# untitled5.net
KiCad netlist of a schematic drawn in EAGLE
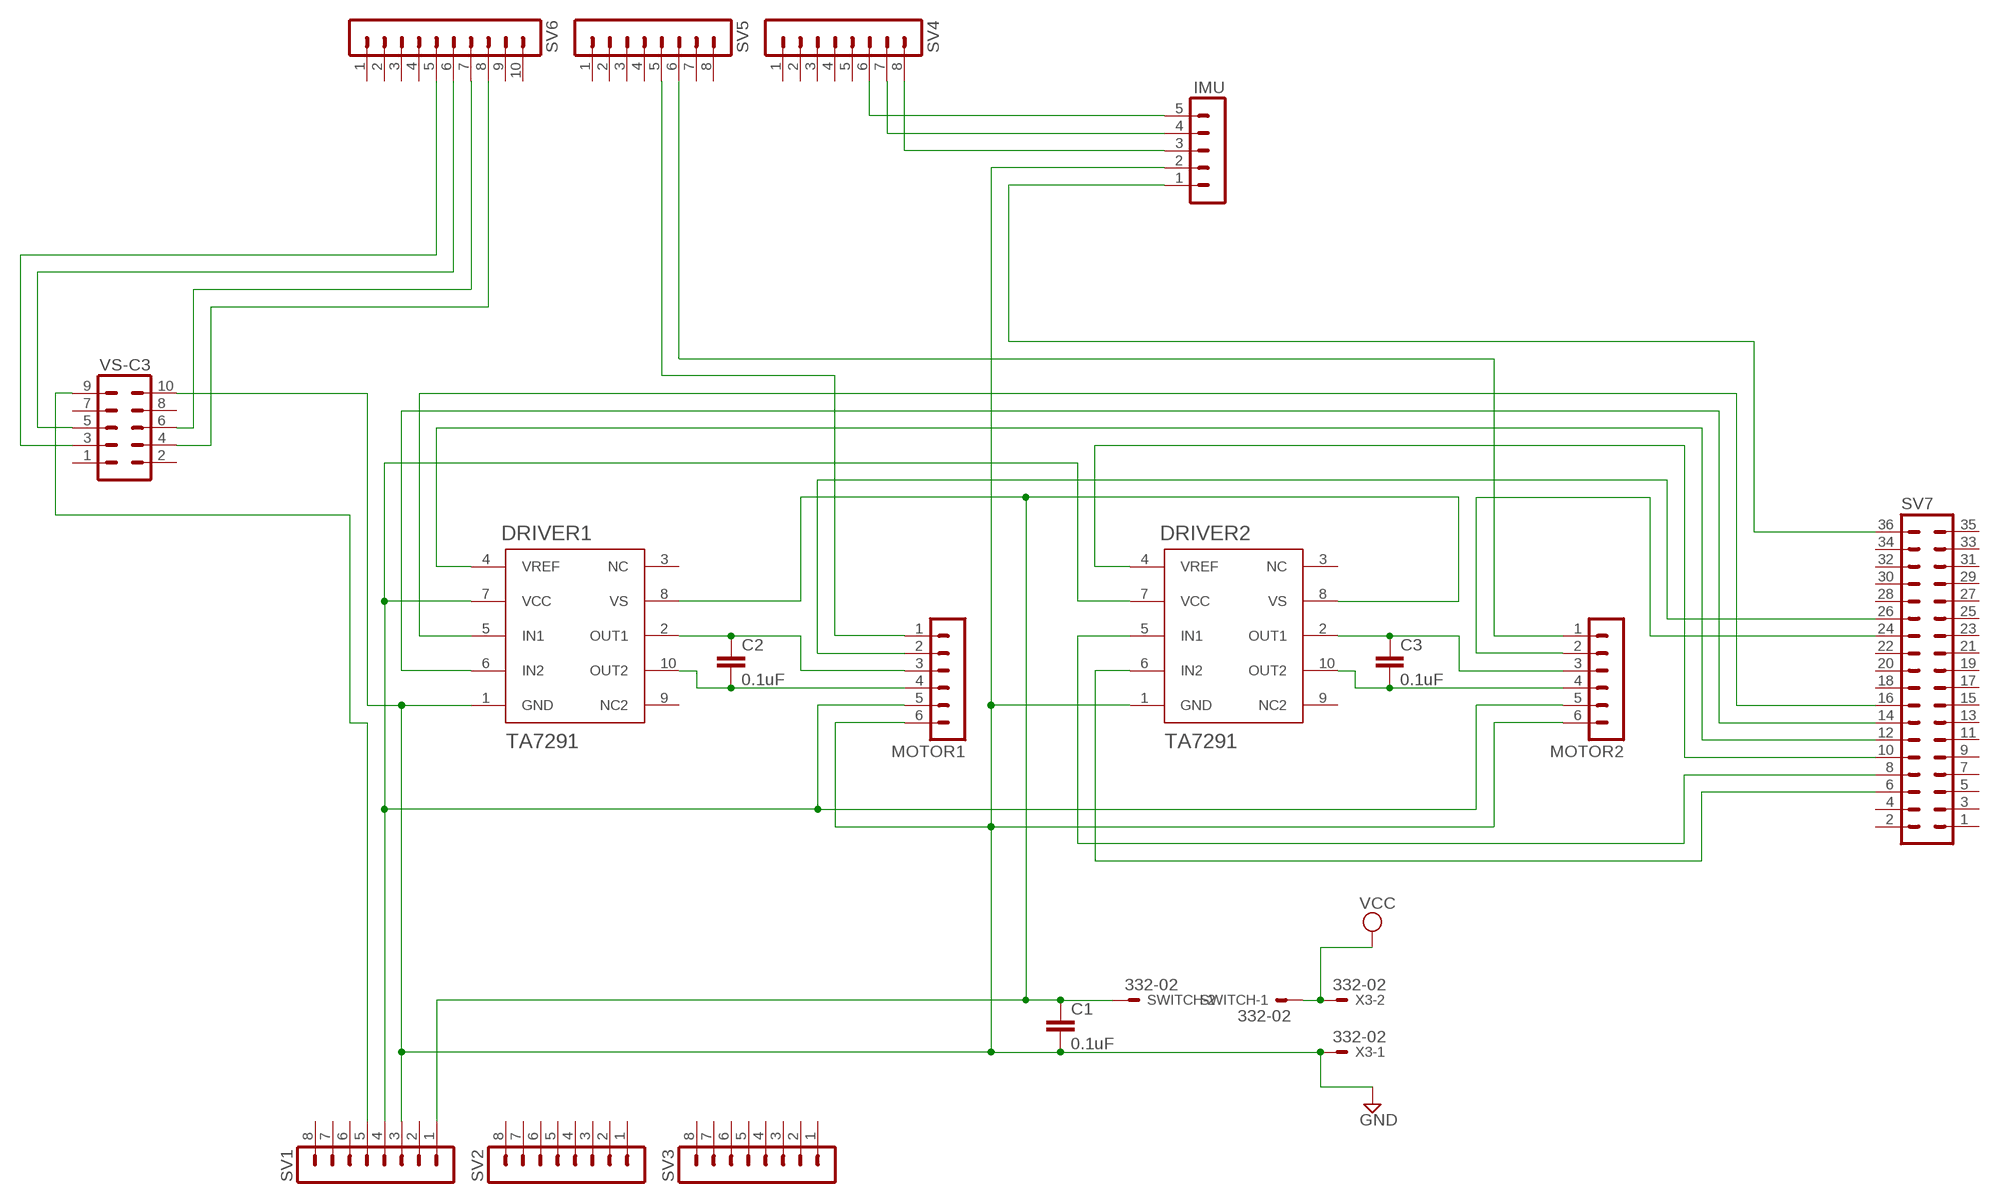
[diagram p0: schematic, sheet 1]

(export (version "E")
  (design (tool "Eeschema 10.0.6"))
  (components
    (comp (ref "C1")
      (value "0.1uF")
      (footprint "eagle-import:C5B2.5")
      (libsource (lib "eagle-import") (part "C5/2.5"))
    )
    (comp (ref "C2")
      (value "0.1uF")
      (footprint "eagle-import:C5B2.5")
      (libsource (lib "eagle-import") (part "C5/2.5"))
    )
    (comp (ref "C3")
      (value "0.1uF")
      (footprint "eagle-import:C5B2.5")
      (libsource (lib "eagle-import") (part "C5/2.5"))
    )
    (comp (ref "DRIVER1")
      (value "TA7291")
      (footprint "eagle-import:HSIP10")
      (libsource (lib "eagle-import") (part "TA7291"))
    )
    (comp (ref "DRIVER2")
      (value "TA7291")
      (footprint "eagle-import:HSIP10")
      (libsource (lib "eagle-import") (part "TA7291"))
    )
    (comp (ref "IMU")
      (value "MA05-1")
      (footprint "eagle-import:MA05-1")
      (libsource (lib "eagle-import") (part "MA05-1"))
    )
    (comp (ref "MOTOR1")
      (value "MA06-1")
      (footprint "eagle-import:MA06-1")
      (libsource (lib "eagle-import") (part "MA06-1"))
    )
    (comp (ref "MOTOR2")
      (value "MA06-1")
      (footprint "eagle-import:MA06-1")
      (libsource (lib "eagle-import") (part "MA06-1"))
    )
    (comp (ref "SV1")
      (value "MA08-1")
      (footprint "eagle-import:MA08-1")
      (libsource (lib "eagle-import") (part "MA08-1"))
    )
    (comp (ref "SV2")
      (value "MA08-1")
      (footprint "eagle-import:MA08-1")
      (libsource (lib "eagle-import") (part "MA08-1"))
    )
    (comp (ref "SV3")
      (value "MA08-1")
      (footprint "eagle-import:MA08-1")
      (libsource (lib "eagle-import") (part "MA08-1"))
    )
    (comp (ref "SV4")
      (value "MA08-1")
      (footprint "eagle-import:MA08-1")
      (libsource (lib "eagle-import") (part "MA08-1"))
    )
    (comp (ref "SV5")
      (value "MA08-1")
      (footprint "eagle-import:MA08-1")
      (libsource (lib "eagle-import") (part "MA08-1"))
    )
    (comp (ref "SV6")
      (value "MA10-1")
      (footprint "eagle-import:MA10-1")
      (libsource (lib "eagle-import") (part "MA10-1"))
    )
    (comp (ref "SV7")
      (value "MA18-2")
      (footprint "eagle-import:MA18-2")
      (libsource (lib "eagle-import") (part "MA18-2"))
    )
    (comp (ref "SWITCH")
      (value "332-02")
      (footprint "eagle-import:332-02")
      (libsource (lib "eagle-import") (part "332-02"))
    )
    (comp (ref "VS-C3")
      (value "MA05-2")
      (footprint "eagle-import:MA05-2")
      (libsource (lib "eagle-import") (part "MA05-2"))
    )
    (comp (ref "X3")
      (value "332-02")
      (footprint "eagle-import:332-02")
      (libsource (lib "eagle-import") (part "332-02"))
    )
  )
  (nets
    (net (code "1") (name "GND") (class "Default")
      (node (ref "C1") (pin "2") (pinfunction "2_2") (pintype "passive"))
      (node (ref "DRIVER1") (pin "1") (pinfunction "GND_1") (pintype "bidirectional"))
      (node (ref "DRIVER2") (pin "1") (pinfunction "GND_1") (pintype "bidirectional"))
      (node (ref "IMU") (pin "2") (pinfunction "2_2") (pintype "passive"))
      (node (ref "MOTOR1") (pin "6") (pinfunction "6_6") (pintype "passive"))
      (node (ref "MOTOR2") (pin "6") (pinfunction "6_6") (pintype "passive"))
      (node (ref "SV1") (pin "3") (pinfunction "3_3") (pintype "passive"))
      (node (ref "VS-C3") (pin "10") (pinfunction "10_10") (pintype "passive"))
      (node (ref "X3") (pin "1") (pinfunction "S_1") (pintype "passive"))
    )
    (net (code "2") (name "Net-(DRIVER1-IN1)") (class "Default")
      (node (ref "DRIVER1") (pin "5") (pinfunction "IN1_5") (pintype "bidirectional"))
      (node (ref "SV7") (pin "16") (pinfunction "16_16") (pintype "passive"))
    )
    (net (code "3") (name "Net-(DRIVER1-IN2)") (class "Default")
      (node (ref "DRIVER1") (pin "6") (pinfunction "IN2_6") (pintype "bidirectional"))
      (node (ref "SV7") (pin "14") (pinfunction "14_14") (pintype "passive"))
    )
    (net (code "4") (name "Net-(DRIVER1-OUT1)") (class "Default")
      (node (ref "C2") (pin "1") (pinfunction "1_1") (pintype "passive"))
      (node (ref "DRIVER1") (pin "2") (pinfunction "OUT1_2") (pintype "bidirectional"))
      (node (ref "MOTOR1") (pin "3") (pinfunction "3_3") (pintype "passive"))
    )
    (net (code "5") (name "Net-(DRIVER1-OUT2)") (class "Default")
      (node (ref "C2") (pin "2") (pinfunction "2_2") (pintype "passive"))
      (node (ref "DRIVER1") (pin "10") (pinfunction "OUT2_10") (pintype "bidirectional"))
      (node (ref "MOTOR1") (pin "4") (pinfunction "4_4") (pintype "passive"))
    )
    (net (code "6") (name "Net-(DRIVER1-VCC)") (class "Default")
      (node (ref "DRIVER1") (pin "7") (pinfunction "VCC_7") (pintype "bidirectional"))
      (node (ref "DRIVER2") (pin "7") (pinfunction "VCC_7") (pintype "bidirectional"))
      (node (ref "MOTOR1") (pin "5") (pinfunction "5_5") (pintype "passive"))
      (node (ref "MOTOR2") (pin "5") (pinfunction "5_5") (pintype "passive"))
      (node (ref "SV1") (pin "4") (pinfunction "4_4") (pintype "passive"))
    )
    (net (code "7") (name "Net-(DRIVER1-VREF)") (class "Default")
      (node (ref "DRIVER1") (pin "4") (pinfunction "VREF_4") (pintype "bidirectional"))
      (node (ref "SV7") (pin "12") (pinfunction "12_12") (pintype "passive"))
    )
    (net (code "8") (name "Net-(DRIVER1-VS)") (class "Default")
      (node (ref "C1") (pin "1") (pinfunction "1_1") (pintype "passive"))
      (node (ref "DRIVER1") (pin "8") (pinfunction "VS_8") (pintype "bidirectional"))
      (node (ref "DRIVER2") (pin "8") (pinfunction "VS_8") (pintype "bidirectional"))
      (node (ref "SV1") (pin "1") (pinfunction "1_1") (pintype "passive"))
      (node (ref "SWITCH") (pin "2") (pinfunction "S_2") (pintype "passive"))
    )
    (net (code "9") (name "Net-(DRIVER2-IN1)") (class "Default")
      (node (ref "DRIVER2") (pin "5") (pinfunction "IN1_5") (pintype "bidirectional"))
      (node (ref "SV7") (pin "8") (pinfunction "8_8") (pintype "passive"))
    )
    (net (code "10") (name "Net-(DRIVER2-IN2)") (class "Default")
      (node (ref "DRIVER2") (pin "6") (pinfunction "IN2_6") (pintype "bidirectional"))
      (node (ref "SV7") (pin "6") (pinfunction "6_6") (pintype "passive"))
    )
    (net (code "11") (name "Net-(DRIVER2-OUT1)") (class "Default")
      (node (ref "C3") (pin "1") (pinfunction "1_1") (pintype "passive"))
      (node (ref "DRIVER2") (pin "2") (pinfunction "OUT1_2") (pintype "bidirectional"))
      (node (ref "MOTOR2") (pin "3") (pinfunction "3_3") (pintype "passive"))
    )
    (net (code "12") (name "Net-(DRIVER2-OUT2)") (class "Default")
      (node (ref "C3") (pin "2") (pinfunction "2_2") (pintype "passive"))
      (node (ref "DRIVER2") (pin "10") (pinfunction "OUT2_10") (pintype "bidirectional"))
      (node (ref "MOTOR2") (pin "4") (pinfunction "4_4") (pintype "passive"))
    )
    (net (code "13") (name "Net-(DRIVER2-VREF)") (class "Default")
      (node (ref "DRIVER2") (pin "4") (pinfunction "VREF_4") (pintype "bidirectional"))
      (node (ref "SV7") (pin "10") (pinfunction "10_10") (pintype "passive"))
    )
    (net (code "14") (name "Net-(IMU-Pad1)") (class "Default")
      (node (ref "IMU") (pin "1") (pinfunction "1_1") (pintype "passive"))
      (node (ref "SV7") (pin "36") (pinfunction "36_36") (pintype "passive"))
    )
    (net (code "15") (name "Net-(IMU-Pad3)") (class "Default")
      (node (ref "IMU") (pin "3") (pinfunction "3_3") (pintype "passive"))
      (node (ref "SV4") (pin "8") (pinfunction "8_8") (pintype "passive"))
    )
    (net (code "16") (name "Net-(IMU-Pad4)") (class "Default")
      (node (ref "IMU") (pin "4") (pinfunction "4_4") (pintype "passive"))
      (node (ref "SV4") (pin "7") (pinfunction "7_7") (pintype "passive"))
    )
    (net (code "17") (name "Net-(IMU-Pad5)") (class "Default")
      (node (ref "IMU") (pin "5") (pinfunction "5_5") (pintype "passive"))
      (node (ref "SV4") (pin "6") (pinfunction "6_6") (pintype "passive"))
    )
    (net (code "18") (name "Net-(MOTOR1-Pad1)") (class "Default")
      (node (ref "MOTOR1") (pin "1") (pinfunction "1_1") (pintype "passive"))
      (node (ref "SV5") (pin "5") (pinfunction "5_5") (pintype "passive"))
    )
    (net (code "19") (name "Net-(MOTOR1-Pad2)") (class "Default")
      (node (ref "MOTOR1") (pin "2") (pinfunction "2_2") (pintype "passive"))
      (node (ref "SV7") (pin "26") (pinfunction "26_26") (pintype "passive"))
    )
    (net (code "20") (name "Net-(MOTOR2-Pad1)") (class "Default")
      (node (ref "MOTOR2") (pin "1") (pinfunction "1_1") (pintype "passive"))
      (node (ref "SV5") (pin "6") (pinfunction "6_6") (pintype "passive"))
    )
    (net (code "21") (name "Net-(MOTOR2-Pad2)") (class "Default")
      (node (ref "MOTOR2") (pin "2") (pinfunction "2_2") (pintype "passive"))
      (node (ref "SV7") (pin "24") (pinfunction "24_24") (pintype "passive"))
    )
    (net (code "22") (name "Net-(SV1-Pad5)") (class "Default")
      (node (ref "SV1") (pin "5") (pinfunction "5_5") (pintype "passive"))
      (node (ref "VS-C3") (pin "9") (pinfunction "9_9") (pintype "passive"))
    )
    (net (code "23") (name "Net-(SV6-Pad5)") (class "Default")
      (node (ref "SV6") (pin "5") (pinfunction "5_5") (pintype "passive"))
      (node (ref "VS-C3") (pin "3") (pinfunction "3_3") (pintype "passive"))
    )
    (net (code "24") (name "Net-(SV6-Pad6)") (class "Default")
      (node (ref "SV6") (pin "6") (pinfunction "6_6") (pintype "passive"))
      (node (ref "VS-C3") (pin "5") (pinfunction "5_5") (pintype "passive"))
    )
    (net (code "25") (name "Net-(SV6-Pad7)") (class "Default")
      (node (ref "SV6") (pin "7") (pinfunction "7_7") (pintype "passive"))
      (node (ref "VS-C3") (pin "6") (pinfunction "6_6") (pintype "passive"))
    )
    (net (code "26") (name "Net-(SV6-Pad8)") (class "Default")
      (node (ref "SV6") (pin "8") (pinfunction "8_8") (pintype "passive"))
      (node (ref "VS-C3") (pin "4") (pinfunction "4_4") (pintype "passive"))
    )
    (net (code "27") (name "VCC") (class "Default")
      (node (ref "SWITCH") (pin "1") (pinfunction "S_1") (pintype "passive"))
      (node (ref "X3") (pin "2") (pinfunction "S_2") (pintype "passive"))
    )
    (net (code "28") (name "unconnected-(DRIVER1-NC-Pad3)") (class "Default")
      (node (ref "DRIVER1") (pin "3") (pinfunction "NC_3") (pintype "bidirectional"))
    )
    (net (code "29") (name "unconnected-(DRIVER1-NC2-Pad9)") (class "Default")
      (node (ref "DRIVER1") (pin "9") (pinfunction "NC2_9") (pintype "bidirectional"))
    )
    (net (code "30") (name "unconnected-(DRIVER2-NC-Pad3)") (class "Default")
      (node (ref "DRIVER2") (pin "3") (pinfunction "NC_3") (pintype "bidirectional"))
    )
    (net (code "31") (name "unconnected-(DRIVER2-NC2-Pad9)") (class "Default")
      (node (ref "DRIVER2") (pin "9") (pinfunction "NC2_9") (pintype "bidirectional"))
    )
    (net (code "32") (name "unconnected-(SV1-Pad2)") (class "Default")
      (node (ref "SV1") (pin "2") (pinfunction "2_2") (pintype "passive"))
    )
    (net (code "33") (name "unconnected-(SV1-Pad6)") (class "Default")
      (node (ref "SV1") (pin "6") (pinfunction "6_6") (pintype "passive"))
    )
    (net (code "34") (name "unconnected-(SV1-Pad7)") (class "Default")
      (node (ref "SV1") (pin "7") (pinfunction "7_7") (pintype "passive"))
    )
    (net (code "35") (name "unconnected-(SV1-Pad8)") (class "Default")
      (node (ref "SV1") (pin "8") (pinfunction "8_8") (pintype "passive"))
    )
    (net (code "36") (name "unconnected-(SV2-Pad1)") (class "Default")
      (node (ref "SV2") (pin "1") (pinfunction "1_1") (pintype "passive"))
    )
    (net (code "37") (name "unconnected-(SV2-Pad2)") (class "Default")
      (node (ref "SV2") (pin "2") (pinfunction "2_2") (pintype "passive"))
    )
    (net (code "38") (name "unconnected-(SV2-Pad3)") (class "Default")
      (node (ref "SV2") (pin "3") (pinfunction "3_3") (pintype "passive"))
    )
    (net (code "39") (name "unconnected-(SV2-Pad4)") (class "Default")
      (node (ref "SV2") (pin "4") (pinfunction "4_4") (pintype "passive"))
    )
    (net (code "40") (name "unconnected-(SV2-Pad5)") (class "Default")
      (node (ref "SV2") (pin "5") (pinfunction "5_5") (pintype "passive"))
    )
    (net (code "41") (name "unconnected-(SV2-Pad6)") (class "Default")
      (node (ref "SV2") (pin "6") (pinfunction "6_6") (pintype "passive"))
    )
    (net (code "42") (name "unconnected-(SV2-Pad7)") (class "Default")
      (node (ref "SV2") (pin "7") (pinfunction "7_7") (pintype "passive"))
    )
    (net (code "43") (name "unconnected-(SV2-Pad8)") (class "Default")
      (node (ref "SV2") (pin "8") (pinfunction "8_8") (pintype "passive"))
    )
    (net (code "44") (name "unconnected-(SV3-Pad1)") (class "Default")
      (node (ref "SV3") (pin "1") (pinfunction "1_1") (pintype "passive"))
    )
    (net (code "45") (name "unconnected-(SV3-Pad2)") (class "Default")
      (node (ref "SV3") (pin "2") (pinfunction "2_2") (pintype "passive"))
    )
    (net (code "46") (name "unconnected-(SV3-Pad3)") (class "Default")
      (node (ref "SV3") (pin "3") (pinfunction "3_3") (pintype "passive"))
    )
    (net (code "47") (name "unconnected-(SV3-Pad4)") (class "Default")
      (node (ref "SV3") (pin "4") (pinfunction "4_4") (pintype "passive"))
    )
    (net (code "48") (name "unconnected-(SV3-Pad5)") (class "Default")
      (node (ref "SV3") (pin "5") (pinfunction "5_5") (pintype "passive"))
    )
    (net (code "49") (name "unconnected-(SV3-Pad6)") (class "Default")
      (node (ref "SV3") (pin "6") (pinfunction "6_6") (pintype "passive"))
    )
    (net (code "50") (name "unconnected-(SV3-Pad7)") (class "Default")
      (node (ref "SV3") (pin "7") (pinfunction "7_7") (pintype "passive"))
    )
    (net (code "51") (name "unconnected-(SV3-Pad8)") (class "Default")
      (node (ref "SV3") (pin "8") (pinfunction "8_8") (pintype "passive"))
    )
    (net (code "52") (name "unconnected-(SV4-Pad1)") (class "Default")
      (node (ref "SV4") (pin "1") (pinfunction "1_1") (pintype "passive"))
    )
    (net (code "53") (name "unconnected-(SV4-Pad2)") (class "Default")
      (node (ref "SV4") (pin "2") (pinfunction "2_2") (pintype "passive"))
    )
    (net (code "54") (name "unconnected-(SV4-Pad3)") (class "Default")
      (node (ref "SV4") (pin "3") (pinfunction "3_3") (pintype "passive"))
    )
    (net (code "55") (name "unconnected-(SV4-Pad4)") (class "Default")
      (node (ref "SV4") (pin "4") (pinfunction "4_4") (pintype "passive"))
    )
    (net (code "56") (name "unconnected-(SV4-Pad5)") (class "Default")
      (node (ref "SV4") (pin "5") (pinfunction "5_5") (pintype "passive"))
    )
    (net (code "57") (name "unconnected-(SV5-Pad1)") (class "Default")
      (node (ref "SV5") (pin "1") (pinfunction "1_1") (pintype "passive"))
    )
    (net (code "58") (name "unconnected-(SV5-Pad2)") (class "Default")
      (node (ref "SV5") (pin "2") (pinfunction "2_2") (pintype "passive"))
    )
    (net (code "59") (name "unconnected-(SV5-Pad3)") (class "Default")
      (node (ref "SV5") (pin "3") (pinfunction "3_3") (pintype "passive"))
    )
    (net (code "60") (name "unconnected-(SV5-Pad4)") (class "Default")
      (node (ref "SV5") (pin "4") (pinfunction "4_4") (pintype "passive"))
    )
    (net (code "61") (name "unconnected-(SV5-Pad7)") (class "Default")
      (node (ref "SV5") (pin "7") (pinfunction "7_7") (pintype "passive"))
    )
    (net (code "62") (name "unconnected-(SV5-Pad8)") (class "Default")
      (node (ref "SV5") (pin "8") (pinfunction "8_8") (pintype "passive"))
    )
    (net (code "63") (name "unconnected-(SV6-Pad1)") (class "Default")
      (node (ref "SV6") (pin "1") (pinfunction "1_1") (pintype "passive"))
    )
    (net (code "64") (name "unconnected-(SV6-Pad2)") (class "Default")
      (node (ref "SV6") (pin "2") (pinfunction "2_2") (pintype "passive"))
    )
    (net (code "65") (name "unconnected-(SV6-Pad3)") (class "Default")
      (node (ref "SV6") (pin "3") (pinfunction "3_3") (pintype "passive"))
    )
    (net (code "66") (name "unconnected-(SV6-Pad4)") (class "Default")
      (node (ref "SV6") (pin "4") (pinfunction "4_4") (pintype "passive"))
    )
    (net (code "67") (name "unconnected-(SV6-Pad9)") (class "Default")
      (node (ref "SV6") (pin "9") (pinfunction "9_9") (pintype "passive"))
    )
    (net (code "68") (name "unconnected-(SV6-Pad10)") (class "Default")
      (node (ref "SV6") (pin "10") (pinfunction "10_10") (pintype "passive"))
    )
    (net (code "69") (name "unconnected-(SV7-Pad1)") (class "Default")
      (node (ref "SV7") (pin "1") (pinfunction "1_1") (pintype "passive"))
    )
    (net (code "70") (name "unconnected-(SV7-Pad2)") (class "Default")
      (node (ref "SV7") (pin "2") (pinfunction "2_2") (pintype "passive"))
    )
    (net (code "71") (name "unconnected-(SV7-Pad3)") (class "Default")
      (node (ref "SV7") (pin "3") (pinfunction "3_3") (pintype "passive"))
    )
    (net (code "72") (name "unconnected-(SV7-Pad4)") (class "Default")
      (node (ref "SV7") (pin "4") (pinfunction "4_4") (pintype "passive"))
    )
    (net (code "73") (name "unconnected-(SV7-Pad5)") (class "Default")
      (node (ref "SV7") (pin "5") (pinfunction "5_5") (pintype "passive"))
    )
    (net (code "74") (name "unconnected-(SV7-Pad7)") (class "Default")
      (node (ref "SV7") (pin "7") (pinfunction "7_7") (pintype "passive"))
    )
    (net (code "75") (name "unconnected-(SV7-Pad9)") (class "Default")
      (node (ref "SV7") (pin "9") (pinfunction "9_9") (pintype "passive"))
    )
    (net (code "76") (name "unconnected-(SV7-Pad11)") (class "Default")
      (node (ref "SV7") (pin "11") (pinfunction "11_11") (pintype "passive"))
    )
    (net (code "77") (name "unconnected-(SV7-Pad13)") (class "Default")
      (node (ref "SV7") (pin "13") (pinfunction "13_13") (pintype "passive"))
    )
    (net (code "78") (name "unconnected-(SV7-Pad15)") (class "Default")
      (node (ref "SV7") (pin "15") (pinfunction "15_15") (pintype "passive"))
    )
    (net (code "79") (name "unconnected-(SV7-Pad17)") (class "Default")
      (node (ref "SV7") (pin "17") (pinfunction "17_17") (pintype "passive"))
    )
    (net (code "80") (name "unconnected-(SV7-Pad18)") (class "Default")
      (node (ref "SV7") (pin "18") (pinfunction "18_18") (pintype "passive"))
    )
    (net (code "81") (name "unconnected-(SV7-Pad19)") (class "Default")
      (node (ref "SV7") (pin "19") (pinfunction "19_19") (pintype "passive"))
    )
    (net (code "82") (name "unconnected-(SV7-Pad20)") (class "Default")
      (node (ref "SV7") (pin "20") (pinfunction "20_20") (pintype "passive"))
    )
    (net (code "83") (name "unconnected-(SV7-Pad21)") (class "Default")
      (node (ref "SV7") (pin "21") (pinfunction "21_21") (pintype "passive"))
    )
    (net (code "84") (name "unconnected-(SV7-Pad22)") (class "Default")
      (node (ref "SV7") (pin "22") (pinfunction "22_22") (pintype "passive"))
    )
    (net (code "85") (name "unconnected-(SV7-Pad23)") (class "Default")
      (node (ref "SV7") (pin "23") (pinfunction "23_23") (pintype "passive"))
    )
    (net (code "86") (name "unconnected-(SV7-Pad25)") (class "Default")
      (node (ref "SV7") (pin "25") (pinfunction "25_25") (pintype "passive"))
    )
    (net (code "87") (name "unconnected-(SV7-Pad27)") (class "Default")
      (node (ref "SV7") (pin "27") (pinfunction "27_27") (pintype "passive"))
    )
    (net (code "88") (name "unconnected-(SV7-Pad28)") (class "Default")
      (node (ref "SV7") (pin "28") (pinfunction "28_28") (pintype "passive"))
    )
    (net (code "89") (name "unconnected-(SV7-Pad29)") (class "Default")
      (node (ref "SV7") (pin "29") (pinfunction "29_29") (pintype "passive"))
    )
    (net (code "90") (name "unconnected-(SV7-Pad30)") (class "Default")
      (node (ref "SV7") (pin "30") (pinfunction "30_30") (pintype "passive"))
    )
    (net (code "91") (name "unconnected-(SV7-Pad31)") (class "Default")
      (node (ref "SV7") (pin "31") (pinfunction "31_31") (pintype "passive"))
    )
    (net (code "92") (name "unconnected-(SV7-Pad32)") (class "Default")
      (node (ref "SV7") (pin "32") (pinfunction "32_32") (pintype "passive"))
    )
    (net (code "93") (name "unconnected-(SV7-Pad33)") (class "Default")
      (node (ref "SV7") (pin "33") (pinfunction "33_33") (pintype "passive"))
    )
    (net (code "94") (name "unconnected-(SV7-Pad34)") (class "Default")
      (node (ref "SV7") (pin "34") (pinfunction "34_34") (pintype "passive"))
    )
    (net (code "95") (name "unconnected-(SV7-Pad35)") (class "Default")
      (node (ref "SV7") (pin "35") (pinfunction "35_35") (pintype "passive"))
    )
    (net (code "96") (name "unconnected-(VS-C3-Pad1)") (class "Default")
      (node (ref "VS-C3") (pin "1") (pinfunction "1_1") (pintype "passive"))
    )
    (net (code "97") (name "unconnected-(VS-C3-Pad2)") (class "Default")
      (node (ref "VS-C3") (pin "2") (pinfunction "2_2") (pintype "passive"))
    )
    (net (code "98") (name "unconnected-(VS-C3-Pad7)") (class "Default")
      (node (ref "VS-C3") (pin "7") (pinfunction "7_7") (pintype "passive"))
    )
    (net (code "99") (name "unconnected-(VS-C3-Pad8)") (class "Default")
      (node (ref "VS-C3") (pin "8") (pinfunction "8_8") (pintype "passive"))
    )
  )
)
